# mcp2515-dip.net
KiCad netlist of a schematic drawn in EAGLE
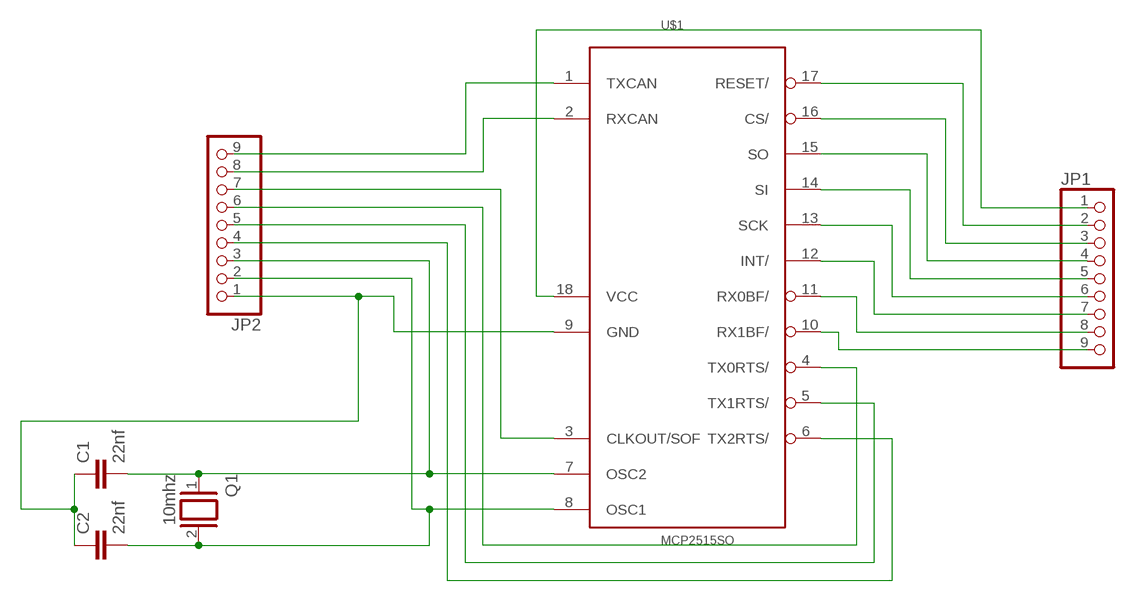
[diagram p0: schematic, sheet 1]

(export (version "E")
  (design (tool "Eeschema 10.0.6"))
  (components
    (comp (ref "C1")
      (value "22nf")
      (footprint "eagle-import:C050-035X075")
      (libsource (lib "eagle-import") (part "C-EU050-035X075"))
    )
    (comp (ref "C2")
      (value "22nf")
      (footprint "eagle-import:C050-035X075")
      (libsource (lib "eagle-import") (part "C-EU050-035X075"))
    )
    (comp (ref "JP1")
      (value "PINHD-1X9")
      (footprint "eagle-import:1X09")
      (libsource (lib "eagle-import") (part "PINHD-1X9"))
    )
    (comp (ref "JP2")
      (value "PINHD-1X9")
      (footprint "eagle-import:1X09")
      (libsource (lib "eagle-import") (part "PINHD-1X9"))
    )
    (comp (ref "Q1")
      (value "10mhz")
      (footprint "eagle-import:QS")
      (libsource (lib "eagle-import") (part "XTAL/S"))
    )
    (comp (ref "U$1")
      (value "MCP2515SO")
      (footprint "eagle-import:SO18L")
      (libsource (lib "eagle-import") (part "MCP2515SO"))
    )
  )
  (nets
    (net (code "1") (name "Net-(U$1-CLKOUT{slash}SOF)") (class "Default")
      (node (ref "JP2") (pin "7") (pinfunction "7_7") (pintype "passive"))
      (node (ref "U$1") (pin "3") (pinfunction "CLKOUT/SOF_3") (pintype "bidirectional"))
    )
    (net (code "2") (name "Net-(U$1-CS{slash})") (class "Default")
      (node (ref "JP1") (pin "3") (pinfunction "3_3") (pintype "passive"))
      (node (ref "U$1") (pin "16") (pinfunction "CS/_16") (pintype "input"))
    )
    (net (code "3") (name "Net-(U$1-GND)") (class "Default")
      (node (ref "C1") (pin "1") (pinfunction "1_1") (pintype "passive"))
      (node (ref "C2") (pin "1") (pinfunction "1_1") (pintype "passive"))
      (node (ref "JP2") (pin "1") (pinfunction "1_1") (pintype "passive"))
      (node (ref "U$1") (pin "9") (pinfunction "GND_9") (pintype "power_in"))
    )
    (net (code "4") (name "Net-(U$1-INT{slash})") (class "Default")
      (node (ref "JP1") (pin "7") (pinfunction "7_7") (pintype "passive"))
      (node (ref "U$1") (pin "12") (pinfunction "INT/_12") (pintype "output"))
    )
    (net (code "5") (name "Net-(U$1-OSC1)") (class "Default")
      (node (ref "C2") (pin "2") (pinfunction "2_2") (pintype "passive"))
      (node (ref "JP2") (pin "2") (pinfunction "2_2") (pintype "passive"))
      (node (ref "Q1") (pin "2") (pinfunction "2_2") (pintype "passive"))
      (node (ref "U$1") (pin "8") (pinfunction "OSC1_8") (pintype "bidirectional"))
    )
    (net (code "6") (name "Net-(U$1-OSC2)") (class "Default")
      (node (ref "C1") (pin "2") (pinfunction "2_2") (pintype "passive"))
      (node (ref "JP2") (pin "3") (pinfunction "3_3") (pintype "passive"))
      (node (ref "Q1") (pin "1") (pinfunction "1_1") (pintype "passive"))
      (node (ref "U$1") (pin "7") (pinfunction "OSC2_7") (pintype "bidirectional"))
    )
    (net (code "7") (name "Net-(U$1-RESET{slash})") (class "Default")
      (node (ref "JP1") (pin "2") (pinfunction "2_2") (pintype "passive"))
      (node (ref "U$1") (pin "17") (pinfunction "RESET/_17") (pintype "input"))
    )
    (net (code "8") (name "Net-(U$1-RX0BF{slash})") (class "Default")
      (node (ref "JP1") (pin "8") (pinfunction "8_8") (pintype "passive"))
      (node (ref "U$1") (pin "11") (pinfunction "RX0BF/_11") (pintype "bidirectional"))
    )
    (net (code "9") (name "Net-(U$1-RX1BF{slash})") (class "Default")
      (node (ref "JP1") (pin "9") (pinfunction "9_9") (pintype "passive"))
      (node (ref "U$1") (pin "10") (pinfunction "RX1BF/_10") (pintype "bidirectional"))
    )
    (net (code "10") (name "Net-(U$1-RXCAN)") (class "Default")
      (node (ref "JP2") (pin "8") (pinfunction "8_8") (pintype "passive"))
      (node (ref "U$1") (pin "2") (pinfunction "RXCAN_2") (pintype "input"))
    )
    (net (code "11") (name "Net-(U$1-SCK)") (class "Default")
      (node (ref "JP1") (pin "6") (pinfunction "6_6") (pintype "passive"))
      (node (ref "U$1") (pin "13") (pinfunction "SCK_13") (pintype "input"))
    )
    (net (code "12") (name "Net-(U$1-SI)") (class "Default")
      (node (ref "JP1") (pin "5") (pinfunction "5_5") (pintype "passive"))
      (node (ref "U$1") (pin "14") (pinfunction "SI_14") (pintype "input"))
    )
    (net (code "13") (name "Net-(U$1-SO)") (class "Default")
      (node (ref "JP1") (pin "4") (pinfunction "4_4") (pintype "passive"))
      (node (ref "U$1") (pin "15") (pinfunction "SO_15") (pintype "output"))
    )
    (net (code "14") (name "Net-(U$1-TX0RTS{slash})") (class "Default")
      (node (ref "JP2") (pin "6") (pinfunction "6_6") (pintype "passive"))
      (node (ref "U$1") (pin "4") (pinfunction "TX0RTS/_4") (pintype "bidirectional"))
    )
    (net (code "15") (name "Net-(U$1-TX1RTS{slash})") (class "Default")
      (node (ref "JP2") (pin "5") (pinfunction "5_5") (pintype "passive"))
      (node (ref "U$1") (pin "5") (pinfunction "TX1RTS/_5") (pintype "bidirectional"))
    )
    (net (code "16") (name "Net-(U$1-TX2RTS{slash})") (class "Default")
      (node (ref "JP2") (pin "4") (pinfunction "4_4") (pintype "passive"))
      (node (ref "U$1") (pin "6") (pinfunction "TX2RTS/_6") (pintype "bidirectional"))
    )
    (net (code "17") (name "Net-(U$1-TXCAN)") (class "Default")
      (node (ref "JP2") (pin "9") (pinfunction "9_9") (pintype "passive"))
      (node (ref "U$1") (pin "1") (pinfunction "TXCAN_1") (pintype "output"))
    )
    (net (code "18") (name "Net-(U$1-VCC)") (class "Default")
      (node (ref "JP1") (pin "1") (pinfunction "1_1") (pintype "passive"))
      (node (ref "U$1") (pin "18") (pinfunction "VCC_18") (pintype "power_in"))
    )
  )
)
